# wiring_layout.net
KiCad netlist of a schematic drawn in EasyEDA
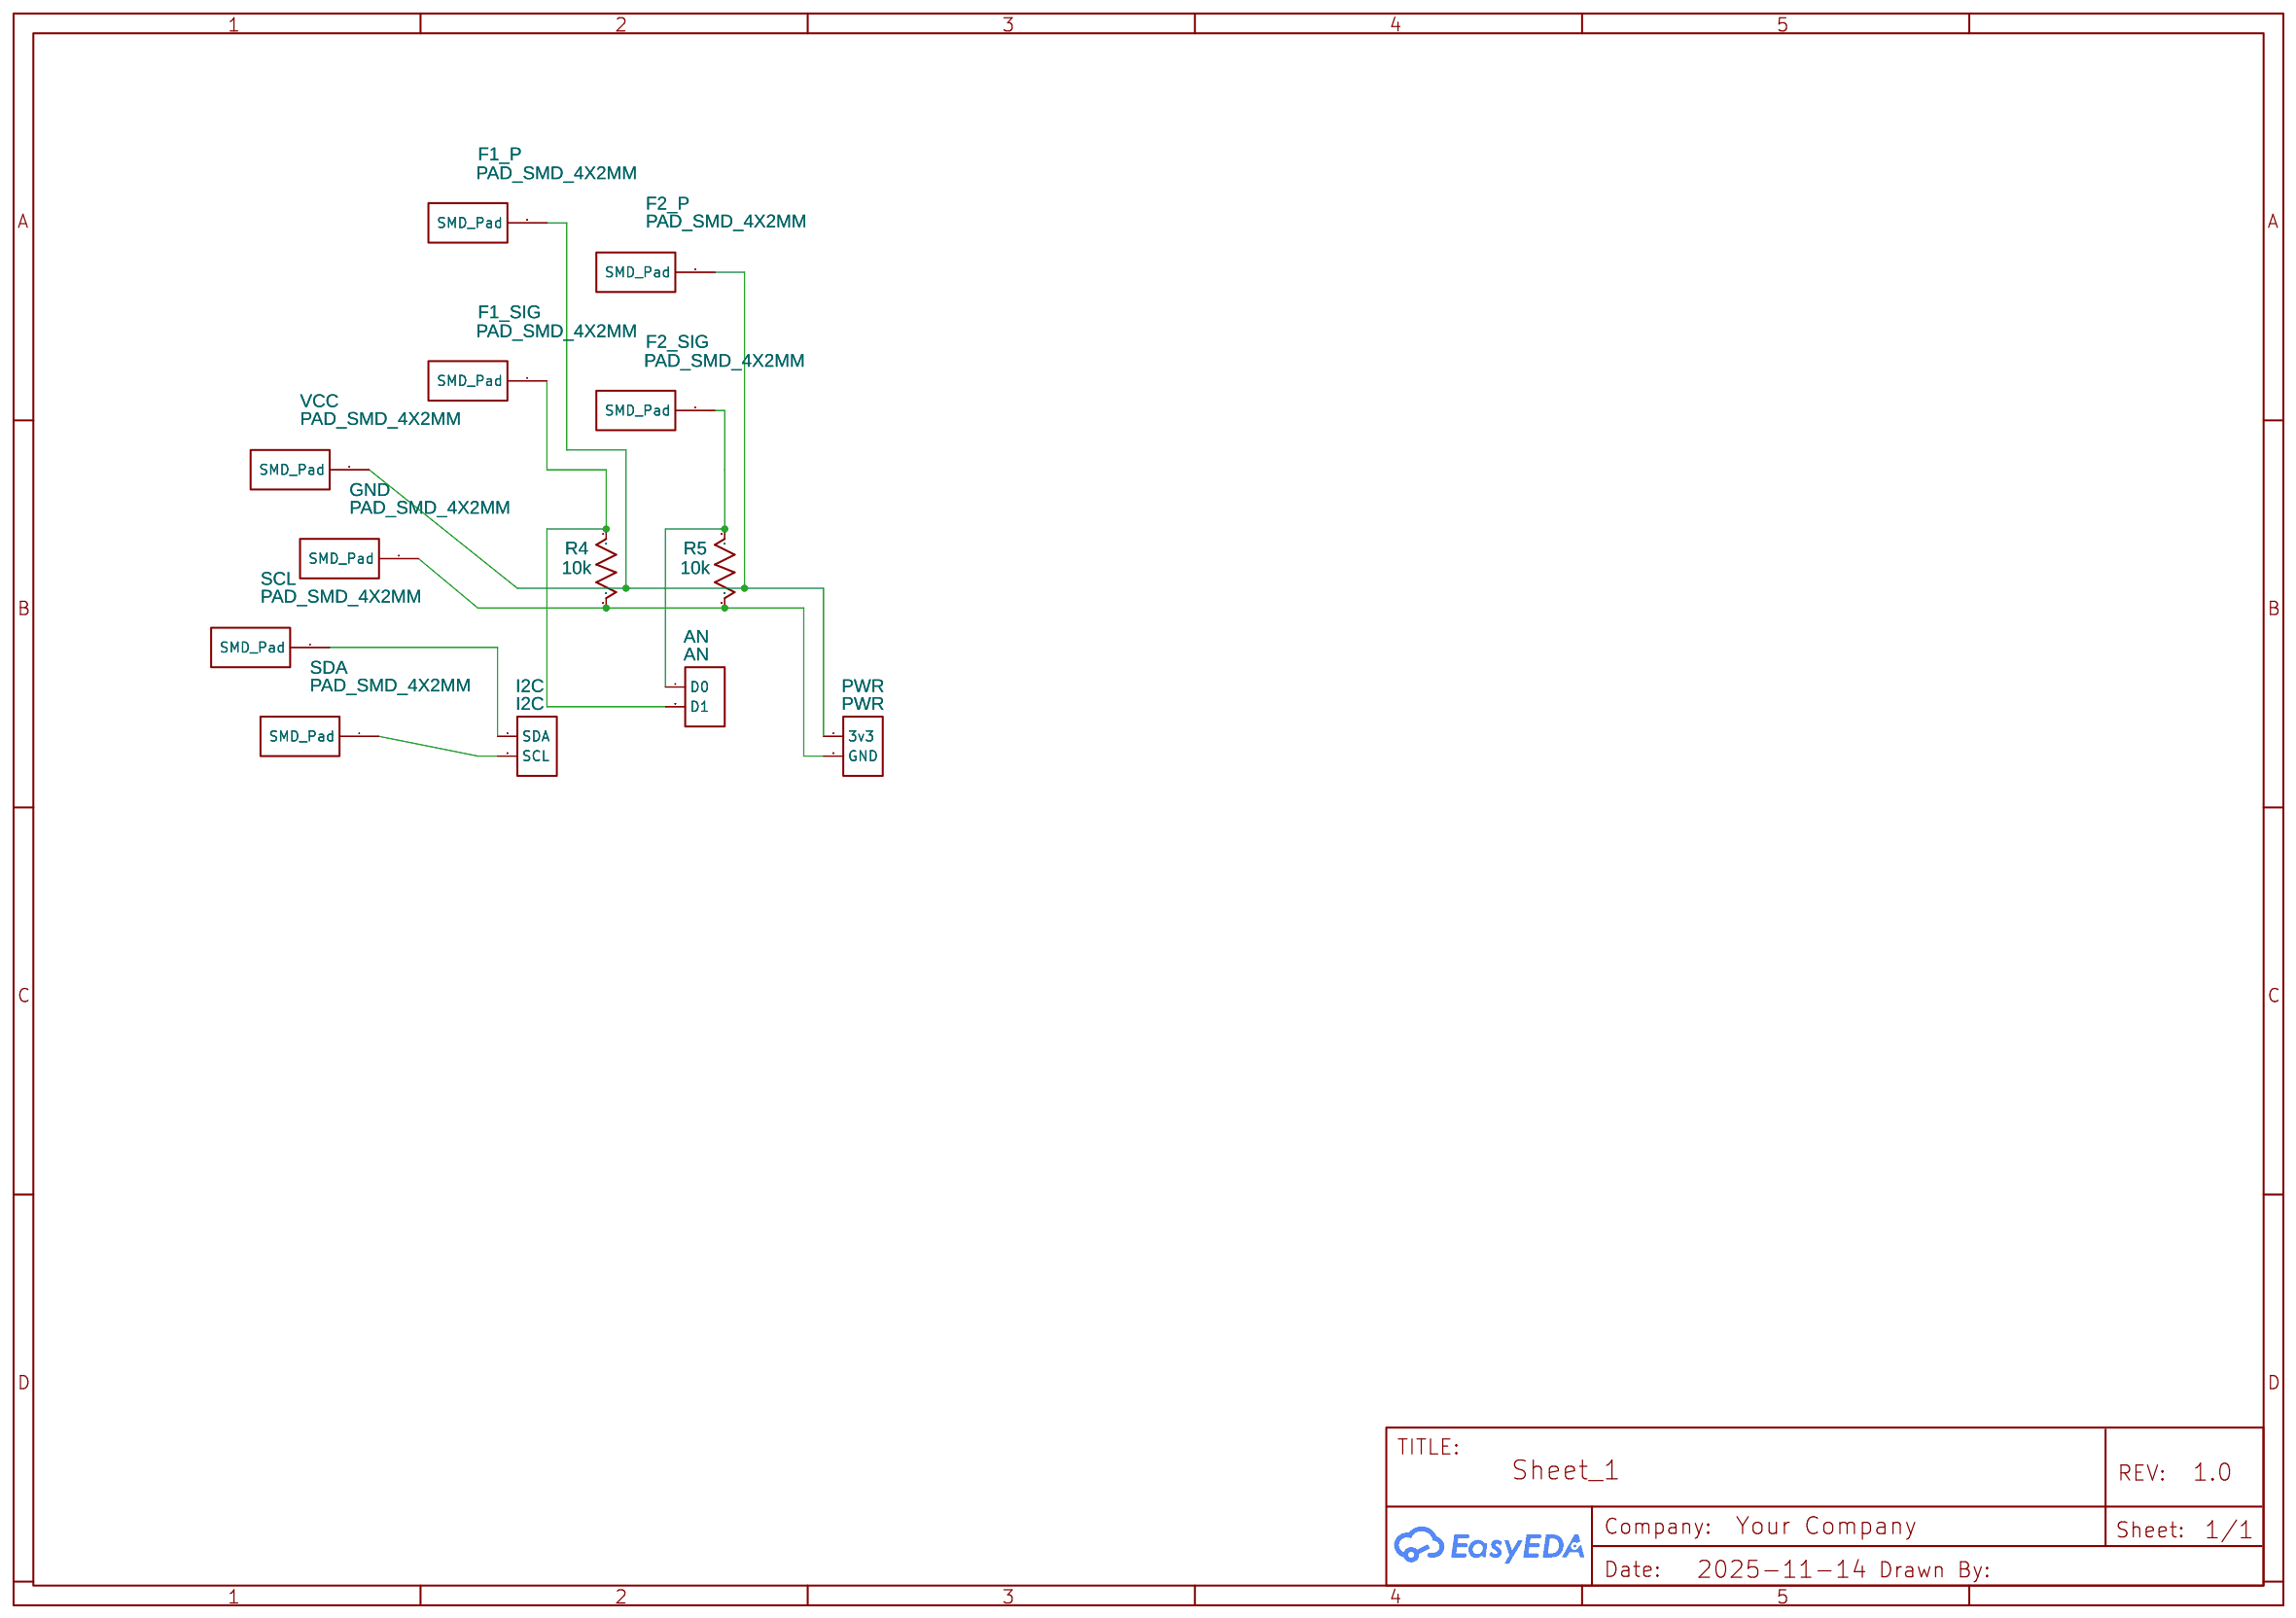
[diagram p0: schematic sheet]

(export (version "E")
  (design (tool "Eeschema 10.0.6"))
  (components
    (comp (ref "AN") (value "AN") (libsource (lib "") (part "HDR-M-2.54_1x2")))
    (comp (ref "F1_P") (value "PAD_SMD_4X2MM") (libsource (lib "") (part "PAD_SMD_4X2MM_3")))
    (comp (ref "F1_SIG") (value "PAD_SMD_4X2MM") (libsource (lib "") (part "PAD_SMD_4X2MM_1")))
    (comp (ref "F2_P") (value "PAD_SMD_4X2MM") (libsource (lib "") (part "PAD_SMD_4X2MM_5")))
    (comp (ref "F2_SIG") (value "PAD_SMD_4X2MM") (libsource (lib "") (part "PAD_SMD_4X2MM")))
    (comp (ref "GND") (value "PAD_SMD_4X2MM") (libsource (lib "") (part "PAD_SMD_4X2MM_7")))
    (comp (ref "I2C") (value "I2C") (libsource (lib "") (part "HDR-M-2.54_1x2_2")))
    (comp (ref "PWR") (value "PWR") (libsource (lib "") (part "HDR-M-2.54_1x2_1")))
    (comp (ref "R4") (value "10k") (libsource (lib "") (part "R_1206_US")))
    (comp (ref "R5") (value "10k") (libsource (lib "") (part "R_1206_US")))
    (comp (ref "SCL") (value "PAD_SMD_4X2MM") (libsource (lib "") (part "PAD_SMD_4X2MM_4")))
    (comp (ref "SDA") (value "PAD_SMD_4X2MM") (libsource (lib "") (part "PAD_SMD_4X2MM_6")))
    (comp (ref "VCC") (value "PAD_SMD_4X2MM") (libsource (lib "") (part "PAD_SMD_4X2MM_2")))
  )
  (nets
    (net (code "1") (name "Net-(AN-D0)") (class "Default")
      (node (ref "AN") (pin "1") (pinfunction "D0_1") (pintype "unspecified"))
      (node (ref "F2_SIG") (pin "1") (pinfunction "SMD_Pad_1") (pintype "unspecified"))
      (node (ref "R5") (pin "1") (pinfunction "1_1") (pintype "unspecified"))
    )
    (net (code "2") (name "Net-(AN-D1)") (class "Default")
      (node (ref "AN") (pin "2") (pinfunction "D1_2") (pintype "unspecified"))
      (node (ref "F1_SIG") (pin "1") (pinfunction "SMD_Pad_1") (pintype "unspecified"))
      (node (ref "R4") (pin "1") (pinfunction "1_1") (pintype "unspecified"))
    )
    (net (code "3") (name "Net-(F1_P-SMD_Pad)") (class "Default")
      (node (ref "F1_P") (pin "1") (pinfunction "SMD_Pad_1") (pintype "unspecified"))
      (node (ref "F2_P") (pin "1") (pinfunction "SMD_Pad_1") (pintype "unspecified"))
      (node (ref "PWR") (pin "1") (pinfunction "3v3_1") (pintype "unspecified"))
      (node (ref "VCC") (pin "1") (pinfunction "SMD_Pad_1") (pintype "unspecified"))
    )
    (net (code "4") (name "Net-(GND-SMD_Pad)") (class "Default")
      (node (ref "GND") (pin "1") (pinfunction "SMD_Pad_1") (pintype "unspecified"))
      (node (ref "PWR") (pin "2") (pinfunction "GND_2") (pintype "unspecified"))
      (node (ref "R4") (pin "2") (pinfunction "2_2") (pintype "unspecified"))
      (node (ref "R5") (pin "2") (pinfunction "2_2") (pintype "unspecified"))
    )
    (net (code "5") (name "Net-(I2C-SCL)") (class "Default")
      (node (ref "I2C") (pin "2") (pinfunction "SCL_2") (pintype "unspecified"))
      (node (ref "SDA") (pin "1") (pinfunction "SMD_Pad_1") (pintype "unspecified"))
    )
    (net (code "6") (name "Net-(I2C-SDA)") (class "Default")
      (node (ref "I2C") (pin "1") (pinfunction "SDA_1") (pintype "unspecified"))
      (node (ref "SCL") (pin "1") (pinfunction "SMD_Pad_1") (pintype "unspecified"))
    )
  )
)
